# jellyFish_schematic.net
KiCad netlist of a schematic drawn in EAGLE
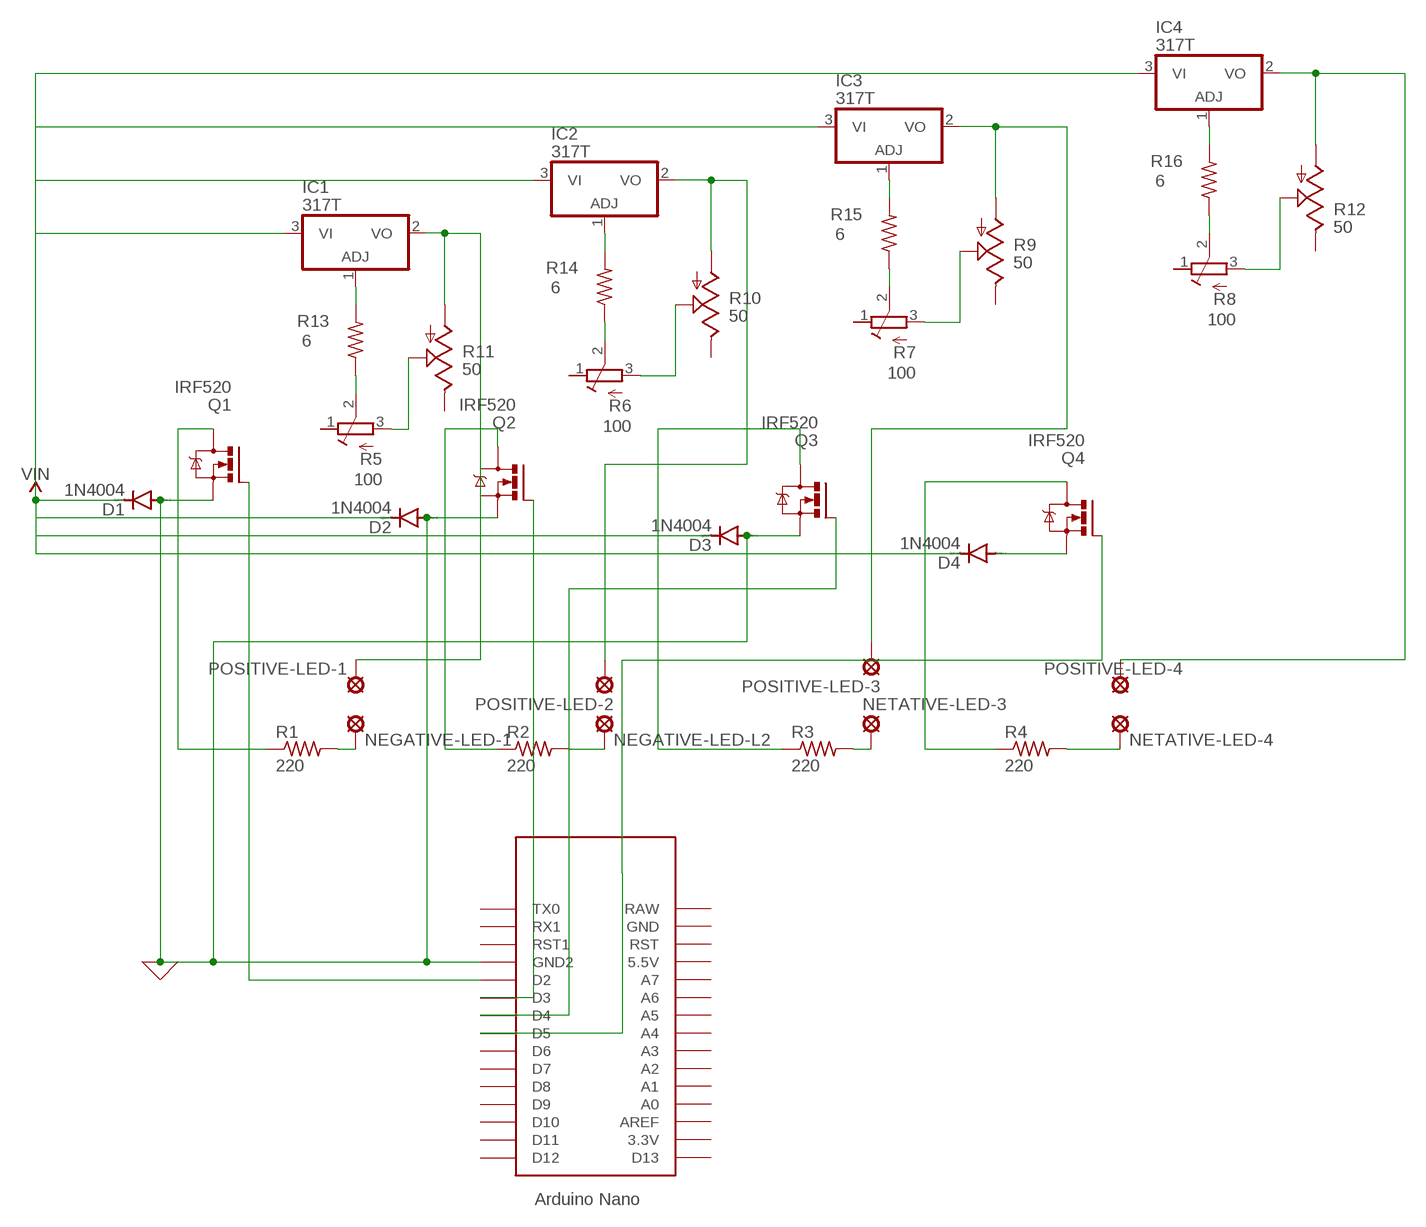
[diagram p0: schematic, sheet 1]

(export (version "E")
  (design (tool "Eeschema 10.0.6"))
  (components
    (comp (ref "D1")
      (value "1N4004")
      (footprint "eagle-import:DO41-10")
      (libsource (lib "eagle-import") (part "1N4004"))
    )
    (comp (ref "D2")
      (value "1N4004")
      (footprint "eagle-import:DO41-10")
      (libsource (lib "eagle-import") (part "1N4004"))
    )
    (comp (ref "D3")
      (value "1N4004")
      (footprint "eagle-import:DO41-10")
      (libsource (lib "eagle-import") (part "1N4004"))
    )
    (comp (ref "D4")
      (value "1N4004")
      (footprint "eagle-import:DO41-10")
      (libsource (lib "eagle-import") (part "1N4004"))
    )
    (comp (ref "IC1")
      (value "317T")
      (footprint "eagle-import:TO220H")
      (libsource (lib "eagle-import") (part "317T"))
    )
    (comp (ref "IC2")
      (value "317T")
      (footprint "eagle-import:TO220H")
      (libsource (lib "eagle-import") (part "317T"))
    )
    (comp (ref "IC3")
      (value "317T")
      (footprint "eagle-import:TO220H")
      (libsource (lib "eagle-import") (part "317T"))
    )
    (comp (ref "IC4")
      (value "317T")
      (footprint "eagle-import:TO220H")
      (libsource (lib "eagle-import") (part "317T"))
    )
    (comp (ref "NEGATIVE-LED-1")
      (value "LSP10")
      (footprint "eagle-import:LSP10")
      (libsource (lib "eagle-import") (part "LSP10"))
    )
    (comp (ref "NEGATIVE-LED-L2")
      (value "LSP10")
      (footprint "eagle-import:LSP10")
      (libsource (lib "eagle-import") (part "LSP10"))
    )
    (comp (ref "NETATIVE-LED-3")
      (value "LSP10")
      (footprint "eagle-import:LSP10")
      (libsource (lib "eagle-import") (part "LSP10"))
    )
    (comp (ref "NETATIVE-LED-4")
      (value "LSP10")
      (footprint "eagle-import:LSP10")
      (libsource (lib "eagle-import") (part "LSP10"))
    )
    (comp (ref "POSITIVE-LED-1")
      (value "POSITIVE LED")
      (footprint "eagle-import:LSP10")
      (libsource (lib "eagle-import") (part "LSP10"))
    )
    (comp (ref "POSITIVE-LED-2")
      (value "LSP10")
      (footprint "eagle-import:LSP10")
      (libsource (lib "eagle-import") (part "LSP10"))
    )
    (comp (ref "POSITIVE-LED-3")
      (value "LSP10")
      (footprint "eagle-import:LSP10")
      (libsource (lib "eagle-import") (part "LSP10"))
    )
    (comp (ref "POSITIVE-LED-4")
      (value "LSP10")
      (footprint "eagle-import:LSP10")
      (libsource (lib "eagle-import") (part "LSP10"))
    )
    (comp (ref "Q1")
      (value "IRF520")
      (footprint "eagle-import:TO220BV")
      (libsource (lib "eagle-import") (part "IRF520"))
    )
    (comp (ref "Q2")
      (value "IRF520")
      (footprint "eagle-import:TO220BV")
      (libsource (lib "eagle-import") (part "IRF520"))
    )
    (comp (ref "Q3")
      (value "IRF520")
      (footprint "eagle-import:TO220BV")
      (libsource (lib "eagle-import") (part "IRF520"))
    )
    (comp (ref "Q4")
      (value "IRF520")
      (footprint "eagle-import:TO220BV")
      (libsource (lib "eagle-import") (part "IRF520"))
    )
    (comp (ref "R1")
      (value "220")
      (footprint "eagle-import:R0805")
      (libsource (lib "eagle-import") (part "R-US_R0805"))
    )
    (comp (ref "R2")
      (value "220")
      (footprint "eagle-import:R0805")
      (libsource (lib "eagle-import") (part "R-US_R0805"))
    )
    (comp (ref "R3")
      (value "220")
      (footprint "eagle-import:R0805")
      (libsource (lib "eagle-import") (part "R-US_R0805"))
    )
    (comp (ref "R4")
      (value "220")
      (footprint "eagle-import:R0805")
      (libsource (lib "eagle-import") (part "R-US_R0805"))
    )
    (comp (ref "R5")
      (value "100")
      (footprint "eagle-import:RTRIMT93YA")
      (libsource (lib "eagle-import") (part "R-TRIMMT93YA"))
    )
    (comp (ref "R6")
      (value "100")
      (footprint "eagle-import:RTRIMT93YA")
      (libsource (lib "eagle-import") (part "R-TRIMMT93YA"))
    )
    (comp (ref "R7")
      (value "100")
      (footprint "eagle-import:RTRIMT93YA")
      (libsource (lib "eagle-import") (part "R-TRIMMT93YA"))
    )
    (comp (ref "R8")
      (value "100")
      (footprint "eagle-import:RTRIMT93YA")
      (libsource (lib "eagle-import") (part "R-TRIMMT93YA"))
    )
    (comp (ref "R9")
      (value "50")
      (footprint "eagle-import:S63P")
      (libsource (lib "eagle-import") (part "TRIM_US-S63P"))
    )
    (comp (ref "R10")
      (value "50")
      (footprint "eagle-import:S63P")
      (libsource (lib "eagle-import") (part "TRIM_US-S63P"))
    )
    (comp (ref "R11")
      (value "50")
      (footprint "eagle-import:S63P")
      (libsource (lib "eagle-import") (part "TRIM_US-S63P"))
    )
    (comp (ref "R12")
      (value "50")
      (footprint "eagle-import:S63P")
      (libsource (lib "eagle-import") (part "TRIM_US-S63P"))
    )
    (comp (ref "R13")
      (value "6")
      (footprint "eagle-import:R0805")
      (libsource (lib "eagle-import") (part "R-US_R0805"))
    )
    (comp (ref "R14")
      (value "6")
      (footprint "eagle-import:R0805")
      (libsource (lib "eagle-import") (part "R-US_R0805"))
    )
    (comp (ref "R15")
      (value "6")
      (footprint "eagle-import:R0805")
      (libsource (lib "eagle-import") (part "R-US_R0805"))
    )
    (comp (ref "R16")
      (value "6")
      (footprint "eagle-import:R0805")
      (libsource (lib "eagle-import") (part "R-US_R0805"))
    )
    (comp (ref "U$1")
      (value "NANO")
      (footprint "eagle-import:NANO")
      (libsource (lib "eagle-import") (part "NANO"))
    )
  )
  (nets
    (net (code "1") (name "GROUND") (class "Default")
      (node (ref "D1") (pin "A") (pinfunction "A_A") (pintype "passive"))
      (node (ref "D2") (pin "A") (pinfunction "A_A") (pintype "passive"))
      (node (ref "D3") (pin "A") (pinfunction "A_A") (pintype "passive"))
      (node (ref "Q1") (pin "S") (pinfunction "S_S") (pintype "passive"))
      (node (ref "Q2") (pin "S") (pinfunction "S_S") (pintype "passive"))
      (node (ref "Q3") (pin "S") (pinfunction "S_S") (pintype "passive"))
      (node (ref "U$1") (pin "GND1") (pinfunction "GND2_GND1") (pintype "bidirectional"))
    )
    (net (code "2") (name "Net-(D4-PadA)") (class "Default")
      (node (ref "D4") (pin "A") (pinfunction "A_A") (pintype "passive"))
      (node (ref "Q4") (pin "S") (pinfunction "S_S") (pintype "passive"))
    )
    (net (code "3") (name "Net-(IC1-ADJ)") (class "Default")
      (node (ref "IC1") (pin "1") (pinfunction "ADJ_1") (pintype "input"))
      (node (ref "R13") (pin "2") (pinfunction "2_2") (pintype "passive"))
    )
    (net (code "4") (name "Net-(IC1-VO)") (class "Default")
      (node (ref "IC1") (pin "2") (pinfunction "VO_2") (pintype "passive"))
      (node (ref "POSITIVE-LED-1") (pin "MP") (pinfunction "MP_MP") (pintype "passive"))
      (node (ref "R11") (pin "A") (pinfunction "A_A") (pintype "passive"))
    )
    (net (code "5") (name "Net-(IC2-ADJ)") (class "Default")
      (node (ref "IC2") (pin "1") (pinfunction "ADJ_1") (pintype "input"))
      (node (ref "R14") (pin "2") (pinfunction "2_2") (pintype "passive"))
    )
    (net (code "6") (name "Net-(IC2-VO)") (class "Default")
      (node (ref "IC2") (pin "2") (pinfunction "VO_2") (pintype "passive"))
      (node (ref "POSITIVE-LED-2") (pin "MP") (pinfunction "MP_MP") (pintype "passive"))
      (node (ref "R10") (pin "A") (pinfunction "A_A") (pintype "passive"))
    )
    (net (code "7") (name "Net-(IC3-ADJ)") (class "Default")
      (node (ref "IC3") (pin "1") (pinfunction "ADJ_1") (pintype "input"))
      (node (ref "R15") (pin "2") (pinfunction "2_2") (pintype "passive"))
    )
    (net (code "8") (name "Net-(IC3-VO)") (class "Default")
      (node (ref "IC3") (pin "2") (pinfunction "VO_2") (pintype "passive"))
      (node (ref "POSITIVE-LED-3") (pin "MP") (pinfunction "MP_MP") (pintype "passive"))
      (node (ref "R9") (pin "A") (pinfunction "A_A") (pintype "passive"))
    )
    (net (code "9") (name "Net-(IC4-ADJ)") (class "Default")
      (node (ref "IC4") (pin "1") (pinfunction "ADJ_1") (pintype "input"))
      (node (ref "R16") (pin "2") (pinfunction "2_2") (pintype "passive"))
    )
    (net (code "10") (name "Net-(IC4-VO)") (class "Default")
      (node (ref "IC4") (pin "2") (pinfunction "VO_2") (pintype "passive"))
      (node (ref "POSITIVE-LED-4") (pin "MP") (pinfunction "MP_MP") (pintype "passive"))
      (node (ref "R12") (pin "A") (pinfunction "A_A") (pintype "passive"))
    )
    (net (code "11") (name "Net-(NEGATIVE-LED-1-PadMP)") (class "Default")
      (node (ref "NEGATIVE-LED-1") (pin "MP") (pinfunction "MP_MP") (pintype "passive"))
      (node (ref "R1") (pin "2") (pinfunction "2_2") (pintype "passive"))
    )
    (net (code "12") (name "Net-(NEGATIVE-LED-L2-PadMP)") (class "Default")
      (node (ref "NEGATIVE-LED-L2") (pin "MP") (pinfunction "MP_MP") (pintype "passive"))
      (node (ref "R2") (pin "2") (pinfunction "2_2") (pintype "passive"))
    )
    (net (code "13") (name "Net-(NETATIVE-LED-3-PadMP)") (class "Default")
      (node (ref "NETATIVE-LED-3") (pin "MP") (pinfunction "MP_MP") (pintype "passive"))
      (node (ref "R3") (pin "2") (pinfunction "2_2") (pintype "passive"))
    )
    (net (code "14") (name "Net-(NETATIVE-LED-4-PadMP)") (class "Default")
      (node (ref "NETATIVE-LED-4") (pin "MP") (pinfunction "MP_MP") (pintype "passive"))
      (node (ref "R4") (pin "2") (pinfunction "2_2") (pintype "passive"))
    )
    (net (code "15") (name "Net-(Q1-PadD)") (class "Default")
      (node (ref "Q1") (pin "D") (pinfunction "D_D") (pintype "passive"))
      (node (ref "R1") (pin "1") (pinfunction "1_1") (pintype "passive"))
    )
    (net (code "16") (name "Net-(Q1-PadG)") (class "Default")
      (node (ref "Q1") (pin "G") (pinfunction "G_G") (pintype "passive"))
      (node (ref "U$1") (pin "D2") (pinfunction "D2_D2") (pintype "bidirectional"))
    )
    (net (code "17") (name "Net-(Q2-PadD)") (class "Default")
      (node (ref "Q2") (pin "D") (pinfunction "D_D") (pintype "passive"))
      (node (ref "R2") (pin "1") (pinfunction "1_1") (pintype "passive"))
    )
    (net (code "18") (name "Net-(Q2-PadG)") (class "Default")
      (node (ref "Q2") (pin "G") (pinfunction "G_G") (pintype "passive"))
      (node (ref "U$1") (pin "D3") (pinfunction "D3_D3") (pintype "bidirectional"))
    )
    (net (code "19") (name "Net-(Q3-PadD)") (class "Default")
      (node (ref "Q3") (pin "D") (pinfunction "D_D") (pintype "passive"))
      (node (ref "R3") (pin "1") (pinfunction "1_1") (pintype "passive"))
    )
    (net (code "20") (name "Net-(Q3-PadG)") (class "Default")
      (node (ref "Q3") (pin "G") (pinfunction "G_G") (pintype "passive"))
      (node (ref "U$1") (pin "D4") (pinfunction "D4_D4") (pintype "bidirectional"))
    )
    (net (code "21") (name "Net-(Q4-PadD)") (class "Default")
      (node (ref "Q4") (pin "D") (pinfunction "D_D") (pintype "passive"))
      (node (ref "R4") (pin "1") (pinfunction "1_1") (pintype "passive"))
    )
    (net (code "22") (name "Net-(Q4-PadG)") (class "Default")
      (node (ref "Q4") (pin "G") (pinfunction "G_G") (pintype "passive"))
      (node (ref "U$1") (pin "D5") (pinfunction "D5_D5") (pintype "bidirectional"))
      (node (ref "U$1") (pin "ICSP1") (pinfunction "ICSP1_ICSP1") (pintype "bidirectional"))
      (node (ref "U$1") (pin "ICSP2") (pinfunction "ICSP2_ICSP2") (pintype "bidirectional"))
    )
    (net (code "23") (name "Net-(R5-A)") (class "Default")
      (node (ref "R11") (pin "S") (pinfunction "S_S") (pintype "passive"))
      (node (ref "R5") (pin "3") (pinfunction "A_3") (pintype "passive"))
    )
    (net (code "24") (name "Net-(R5-S)") (class "Default")
      (node (ref "R13") (pin "1") (pinfunction "1_1") (pintype "passive"))
      (node (ref "R5") (pin "2") (pinfunction "S_2") (pintype "passive"))
    )
    (net (code "25") (name "Net-(R6-A)") (class "Default")
      (node (ref "R10") (pin "S") (pinfunction "S_S") (pintype "passive"))
      (node (ref "R6") (pin "3") (pinfunction "A_3") (pintype "passive"))
    )
    (net (code "26") (name "Net-(R6-S)") (class "Default")
      (node (ref "R14") (pin "1") (pinfunction "1_1") (pintype "passive"))
      (node (ref "R6") (pin "2") (pinfunction "S_2") (pintype "passive"))
    )
    (net (code "27") (name "Net-(R7-A)") (class "Default")
      (node (ref "R7") (pin "3") (pinfunction "A_3") (pintype "passive"))
      (node (ref "R9") (pin "S") (pinfunction "S_S") (pintype "passive"))
    )
    (net (code "28") (name "Net-(R7-S)") (class "Default")
      (node (ref "R15") (pin "1") (pinfunction "1_1") (pintype "passive"))
      (node (ref "R7") (pin "2") (pinfunction "S_2") (pintype "passive"))
    )
    (net (code "29") (name "Net-(R8-A)") (class "Default")
      (node (ref "R12") (pin "S") (pinfunction "S_S") (pintype "passive"))
      (node (ref "R8") (pin "3") (pinfunction "A_3") (pintype "passive"))
    )
    (net (code "30") (name "Net-(R8-S)") (class "Default")
      (node (ref "R16") (pin "1") (pinfunction "1_1") (pintype "passive"))
      (node (ref "R8") (pin "2") (pinfunction "S_2") (pintype "passive"))
    )
    (net (code "31") (name "VIN") (class "Default")
      (node (ref "D1") (pin "C") (pinfunction "C_C") (pintype "passive"))
      (node (ref "D2") (pin "C") (pinfunction "C_C") (pintype "passive"))
      (node (ref "D3") (pin "C") (pinfunction "C_C") (pintype "passive"))
      (node (ref "D4") (pin "C") (pinfunction "C_C") (pintype "passive"))
      (node (ref "IC1") (pin "3") (pinfunction "VI_3") (pintype "input"))
      (node (ref "IC2") (pin "3") (pinfunction "VI_3") (pintype "input"))
      (node (ref "IC3") (pin "3") (pinfunction "VI_3") (pintype "input"))
      (node (ref "IC4") (pin "3") (pinfunction "VI_3") (pintype "input"))
    )
    (net (code "32") (name "unconnected-(R5-E-Pad1)") (class "Default")
      (node (ref "R5") (pin "1") (pinfunction "E_1") (pintype "passive"))
    )
    (net (code "33") (name "unconnected-(R6-E-Pad1)") (class "Default")
      (node (ref "R6") (pin "1") (pinfunction "E_1") (pintype "passive"))
    )
    (net (code "34") (name "unconnected-(R7-E-Pad1)") (class "Default")
      (node (ref "R7") (pin "1") (pinfunction "E_1") (pintype "passive"))
    )
    (net (code "35") (name "unconnected-(R8-E-Pad1)") (class "Default")
      (node (ref "R8") (pin "1") (pinfunction "E_1") (pintype "passive"))
    )
    (net (code "36") (name "unconnected-(R9-PadE)") (class "Default")
      (node (ref "R9") (pin "E") (pinfunction "E_E") (pintype "passive"))
    )
    (net (code "37") (name "unconnected-(R10-PadE)") (class "Default")
      (node (ref "R10") (pin "E") (pinfunction "E_E") (pintype "passive"))
    )
    (net (code "38") (name "unconnected-(R11-PadE)") (class "Default")
      (node (ref "R11") (pin "E") (pinfunction "E_E") (pintype "passive"))
    )
    (net (code "39") (name "unconnected-(R12-PadE)") (class "Default")
      (node (ref "R12") (pin "E") (pinfunction "E_E") (pintype "passive"))
    )
    (net (code "40") (name "unconnected-(U$1-5.5V-Pad5V)") (class "Default")
      (node (ref "U$1") (pin "5V") (pinfunction "5.5V_5V") (pintype "bidirectional"))
    )
    (net (code "41") (name "unconnected-(U$1-Pad3.3V)") (class "Default")
      (node (ref "U$1") (pin "3.3V") (pinfunction "3.3V_3.3V") (pintype "bidirectional"))
    )
    (net (code "42") (name "unconnected-(U$1-PadA0)") (class "Default")
      (node (ref "U$1") (pin "A0") (pinfunction "A0_A0") (pintype "bidirectional"))
    )
    (net (code "43") (name "unconnected-(U$1-PadA1)") (class "Default")
      (node (ref "U$1") (pin "A1") (pinfunction "A1_A1") (pintype "bidirectional"))
    )
    (net (code "44") (name "unconnected-(U$1-PadA2)") (class "Default")
      (node (ref "U$1") (pin "A2") (pinfunction "A2_A2") (pintype "bidirectional"))
    )
    (net (code "45") (name "unconnected-(U$1-PadA3)") (class "Default")
      (node (ref "U$1") (pin "A3") (pinfunction "A3_A3") (pintype "bidirectional"))
    )
    (net (code "46") (name "unconnected-(U$1-PadA4)") (class "Default")
      (node (ref "U$1") (pin "A4") (pinfunction "A4_A4") (pintype "bidirectional"))
    )
    (net (code "47") (name "unconnected-(U$1-PadA5)") (class "Default")
      (node (ref "U$1") (pin "A5") (pinfunction "A5_A5") (pintype "bidirectional"))
    )
    (net (code "48") (name "unconnected-(U$1-PadA6)") (class "Default")
      (node (ref "U$1") (pin "A6") (pinfunction "A6_A6") (pintype "bidirectional"))
    )
    (net (code "49") (name "unconnected-(U$1-PadA7)") (class "Default")
      (node (ref "U$1") (pin "A7") (pinfunction "A7_A7") (pintype "bidirectional"))
    )
    (net (code "50") (name "unconnected-(U$1-PadAREF)") (class "Default")
      (node (ref "U$1") (pin "AREF") (pinfunction "AREF_AREF") (pintype "bidirectional"))
    )
    (net (code "51") (name "unconnected-(U$1-PadD6)") (class "Default")
      (node (ref "U$1") (pin "D6") (pinfunction "D6_D6") (pintype "bidirectional"))
    )
    (net (code "52") (name "unconnected-(U$1-PadD7)") (class "Default")
      (node (ref "U$1") (pin "D7") (pinfunction "D7_D7") (pintype "bidirectional"))
    )
    (net (code "53") (name "unconnected-(U$1-PadD8)") (class "Default")
      (node (ref "U$1") (pin "D8") (pinfunction "D8_D8") (pintype "bidirectional"))
    )
    (net (code "54") (name "unconnected-(U$1-PadD9)") (class "Default")
      (node (ref "U$1") (pin "D9") (pinfunction "D9_D9") (pintype "bidirectional"))
    )
    (net (code "55") (name "unconnected-(U$1-PadD10)") (class "Default")
      (node (ref "U$1") (pin "D10") (pinfunction "D10_D10") (pintype "bidirectional"))
    )
    (net (code "56") (name "unconnected-(U$1-PadD11)") (class "Default")
      (node (ref "U$1") (pin "D11") (pinfunction "D11_D11") (pintype "bidirectional"))
    )
    (net (code "57") (name "unconnected-(U$1-PadD12)") (class "Default")
      (node (ref "U$1") (pin "D12") (pinfunction "D12_D12") (pintype "bidirectional"))
    )
    (net (code "58") (name "unconnected-(U$1-PadD13)") (class "Default")
      (node (ref "U$1") (pin "D13") (pinfunction "D13_D13") (pintype "bidirectional"))
    )
    (net (code "59") (name "unconnected-(U$1-PadGND)") (class "Default")
      (node (ref "U$1") (pin "GND") (pinfunction "GND_GND") (pintype "bidirectional"))
    )
    (net (code "60") (name "unconnected-(U$1-PadICSP3)") (class "Default")
      (node (ref "U$1") (pin "ICSP3") (pinfunction "ICSP3_ICSP3") (pintype "bidirectional"))
    )
    (net (code "61") (name "unconnected-(U$1-PadICSP4)") (class "Default")
      (node (ref "U$1") (pin "ICSP4") (pinfunction "ICSP4_ICSP4") (pintype "bidirectional"))
    )
    (net (code "62") (name "unconnected-(U$1-PadICSP5)") (class "Default")
      (node (ref "U$1") (pin "ICSP5") (pinfunction "ICSP5_ICSP5") (pintype "bidirectional"))
    )
    (net (code "63") (name "unconnected-(U$1-PadICSP6)") (class "Default")
      (node (ref "U$1") (pin "ICSP6") (pinfunction "ICSP6_ICSP6") (pintype "bidirectional"))
    )
    (net (code "64") (name "unconnected-(U$1-PadRAW)") (class "Default")
      (node (ref "U$1") (pin "RAW") (pinfunction "RAW_RAW") (pintype "bidirectional"))
    )
    (net (code "65") (name "unconnected-(U$1-PadRST)") (class "Default")
      (node (ref "U$1") (pin "RST") (pinfunction "RST_RST") (pintype "bidirectional"))
    )
    (net (code "66") (name "unconnected-(U$1-PadRST1)") (class "Default")
      (node (ref "U$1") (pin "RST1") (pinfunction "RST1_RST1") (pintype "bidirectional"))
    )
    (net (code "67") (name "unconnected-(U$1-PadRX1)") (class "Default")
      (node (ref "U$1") (pin "RX1") (pinfunction "RX1_RX1") (pintype "bidirectional"))
    )
    (net (code "68") (name "unconnected-(U$1-PadTX0)") (class "Default")
      (node (ref "U$1") (pin "TX0") (pinfunction "TX0_TX0") (pintype "bidirectional"))
    )
  )
)
